# ADC.net
KiCad netlist of a schematic drawn in Altium Designer
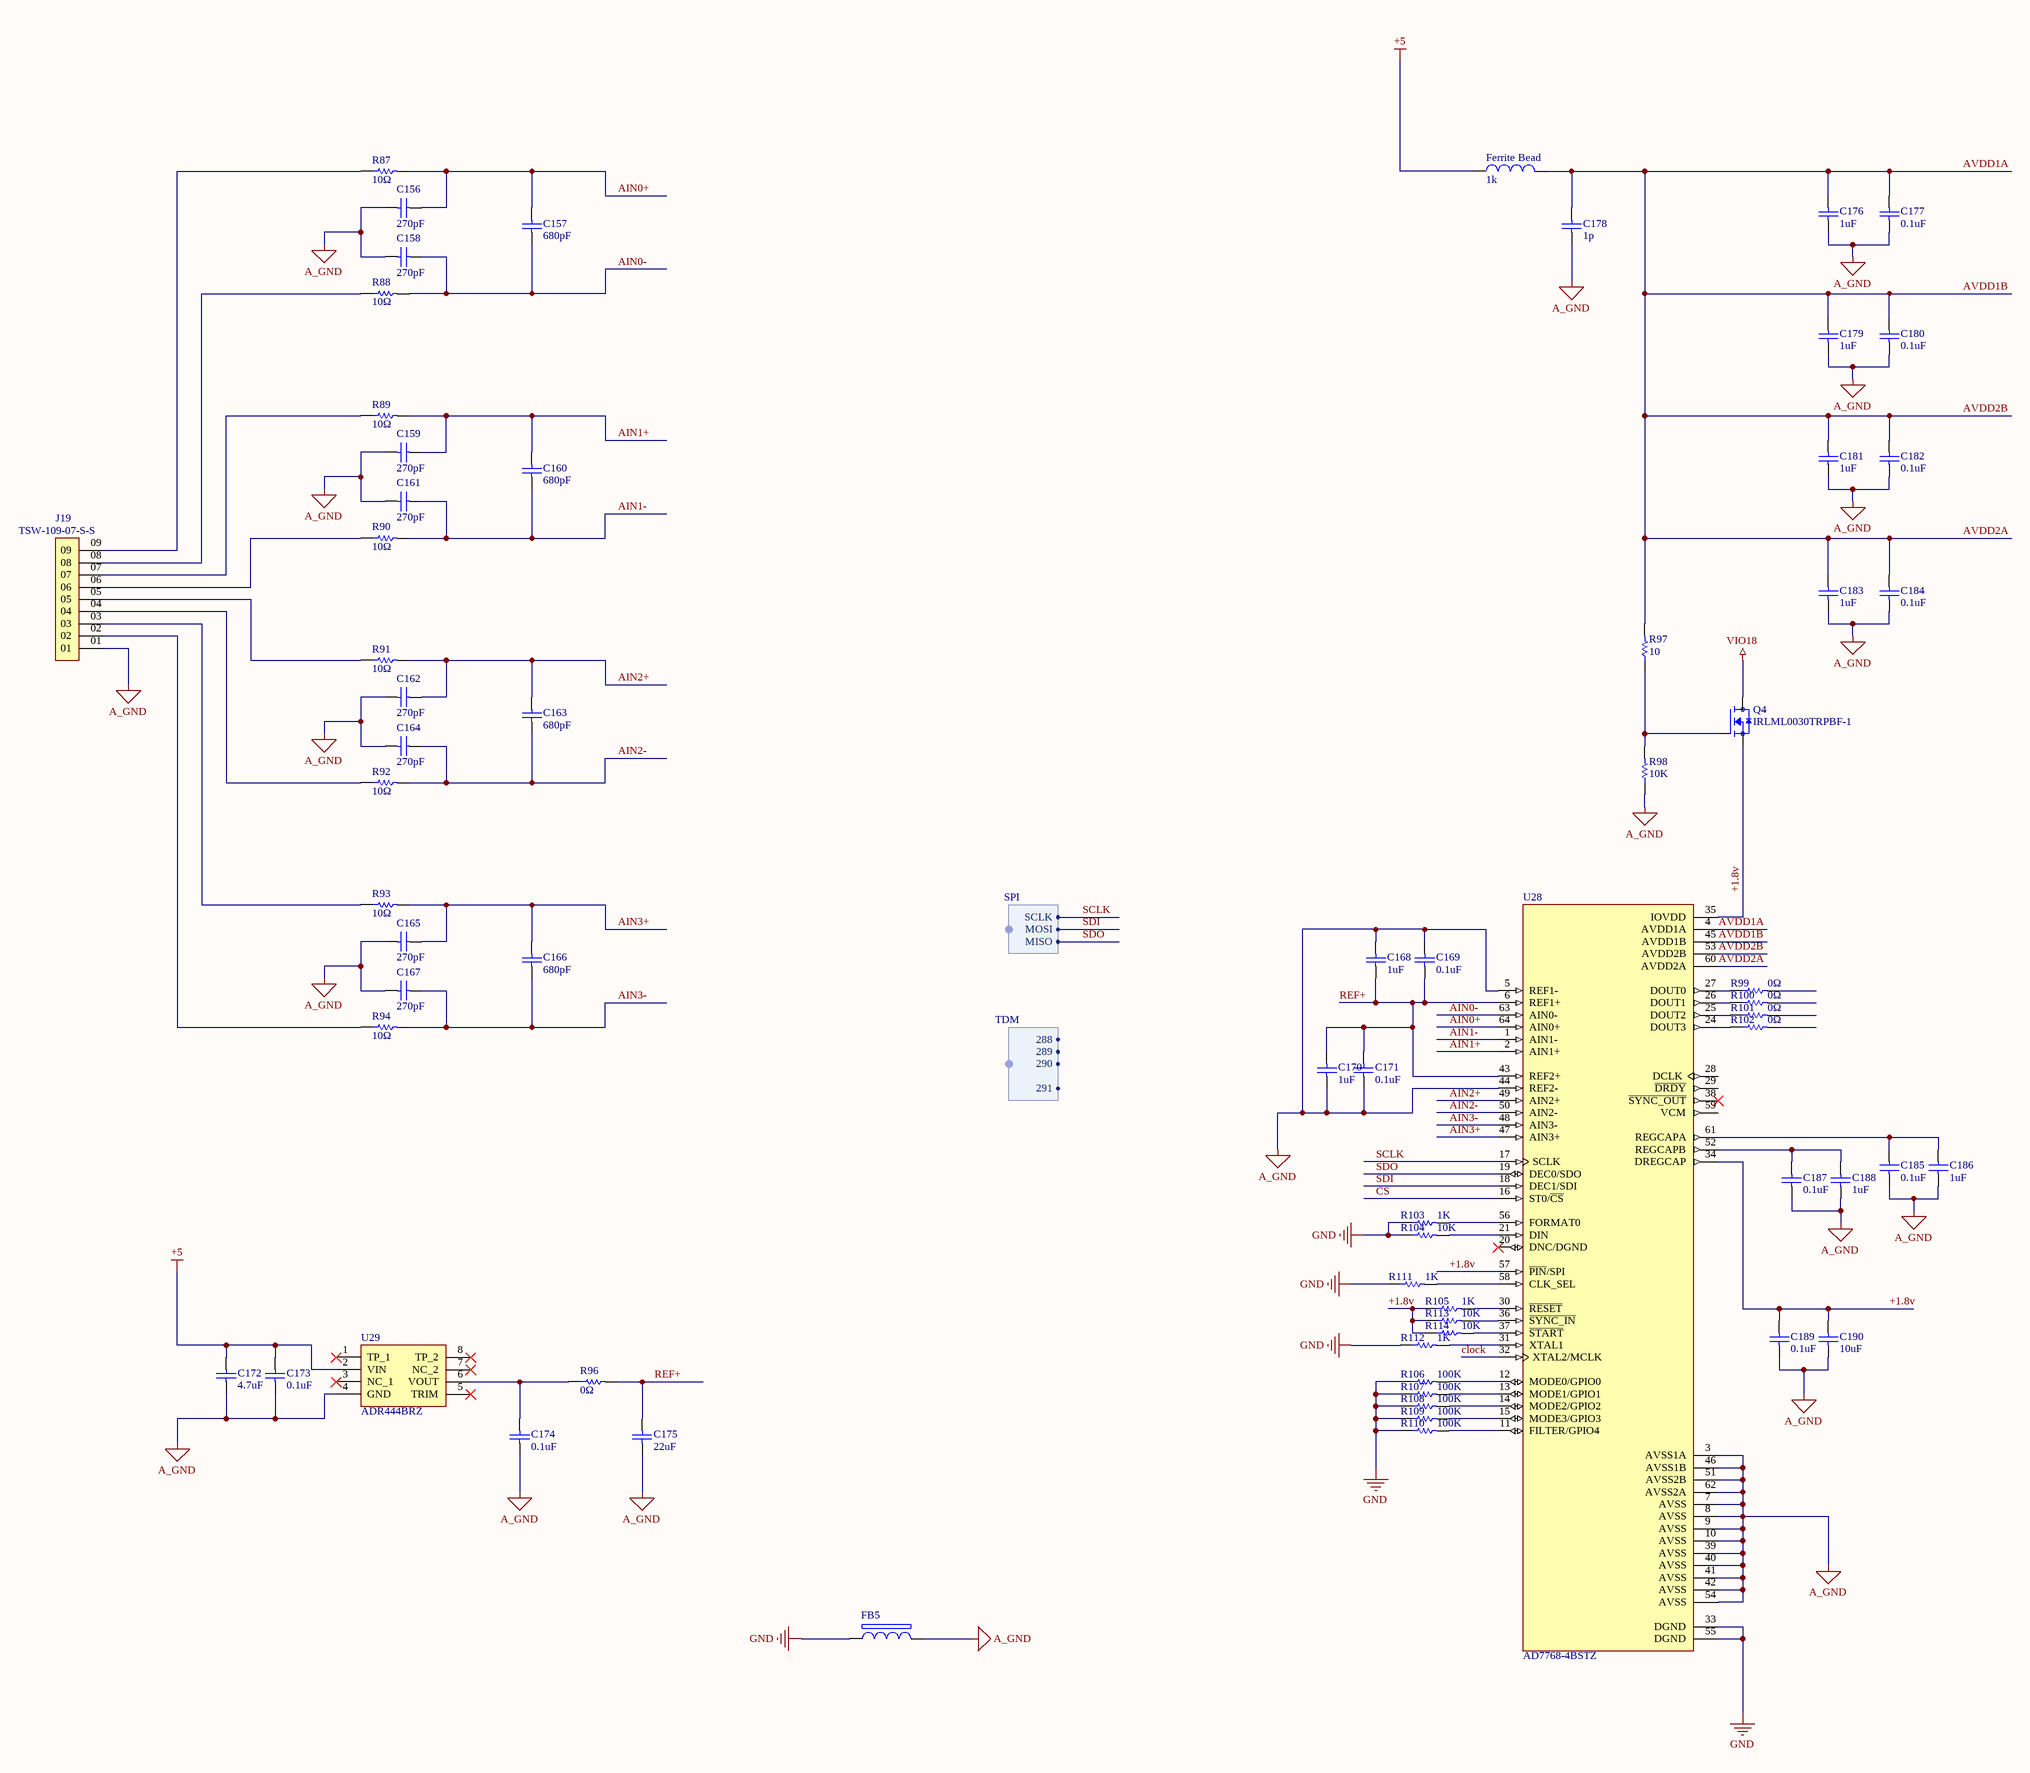
[diagram p0: ADC.SchDoc]

(export (version "E")
  (design (tool "Eeschema 10.0.6"))
  (components
    (comp (ref "C156")
      (value "270pF")
      (description "Capacitor")
      (libsource (lib "Simulation Generic Components") (part "Capacitor"))
    )
    (comp (ref "C157")
      (value "680pF")
      (description "Capacitor")
      (libsource (lib "Simulation Generic Components") (part "Capacitor"))
    )
    (comp (ref "C158")
      (value "270pF")
      (description "Capacitor")
      (libsource (lib "Simulation Generic Components") (part "Capacitor"))
    )
    (comp (ref "C159")
      (value "270pF")
      (description "Capacitor")
      (libsource (lib "Simulation Generic Components") (part "Capacitor"))
    )
    (comp (ref "C160")
      (value "680pF")
      (description "Capacitor")
      (libsource (lib "Simulation Generic Components") (part "Capacitor"))
    )
    (comp (ref "C161")
      (value "270pF")
      (description "Capacitor")
      (libsource (lib "Simulation Generic Components") (part "Capacitor"))
    )
    (comp (ref "C162")
      (value "270pF")
      (description "Capacitor")
      (libsource (lib "Simulation Generic Components") (part "Capacitor"))
    )
    (comp (ref "C163")
      (value "680pF")
      (description "Capacitor")
      (libsource (lib "Simulation Generic Components") (part "Capacitor"))
    )
    (comp (ref "C164")
      (value "270pF")
      (description "Capacitor")
      (libsource (lib "Simulation Generic Components") (part "Capacitor"))
    )
    (comp (ref "C165")
      (value "270pF")
      (description "Capacitor")
      (libsource (lib "Simulation Generic Components") (part "Capacitor"))
    )
    (comp (ref "C166")
      (value "680pF")
      (description "Capacitor")
      (libsource (lib "Simulation Generic Components") (part "Capacitor"))
    )
    (comp (ref "C167")
      (value "270pF")
      (description "Capacitor")
      (libsource (lib "Simulation Generic Components") (part "Capacitor"))
    )
    (comp (ref "C168")
      (value "1uF")
      (description "Capacitor")
      (libsource (lib "Simulation Generic Components") (part "Capacitor"))
    )
    (comp (ref "C169")
      (value "0.1uF")
      (description "Capacitor")
      (libsource (lib "Simulation Generic Components") (part "Capacitor"))
    )
    (comp (ref "C170")
      (value "1uF")
      (description "Capacitor")
      (libsource (lib "Simulation Generic Components") (part "Capacitor"))
    )
    (comp (ref "C171")
      (value "0.1uF")
      (description "Capacitor")
      (libsource (lib "Simulation Generic Components") (part "Capacitor"))
    )
    (comp (ref "C172")
      (value "4.7uF")
      (description "Capacitor")
      (libsource (lib "Simulation Generic Components") (part "Capacitor"))
    )
    (comp (ref "C173")
      (value "0.1uF")
      (description "Capacitor")
      (libsource (lib "Simulation Generic Components") (part "Capacitor"))
    )
    (comp (ref "C174")
      (value "0.1uF")
      (description "Capacitor")
      (libsource (lib "Simulation Generic Components") (part "Capacitor"))
    )
    (comp (ref "C175")
      (value "22uF")
      (description "Capacitor")
      (libsource (lib "Simulation Generic Components") (part "Capacitor"))
    )
    (comp (ref "C176")
      (value "1uF")
      (description "Capacitor")
      (libsource (lib "Simulation Generic Components") (part "Capacitor"))
    )
    (comp (ref "C177")
      (value "0.1uF")
      (description "Capacitor")
      (libsource (lib "Simulation Generic Components") (part "Capacitor"))
    )
    (comp (ref "C178")
      (value "1p")
      (description "Capacitor")
      (libsource (lib "Simulation Generic Components") (part "Capacitor"))
    )
    (comp (ref "C179")
      (value "1uF")
      (description "Capacitor")
      (libsource (lib "Simulation Generic Components") (part "Capacitor"))
    )
    (comp (ref "C180")
      (value "0.1uF")
      (description "Capacitor")
      (libsource (lib "Simulation Generic Components") (part "Capacitor"))
    )
    (comp (ref "C181")
      (value "1uF")
      (description "Capacitor")
      (libsource (lib "Simulation Generic Components") (part "Capacitor"))
    )
    (comp (ref "C182")
      (value "0.1uF")
      (description "Capacitor")
      (libsource (lib "Simulation Generic Components") (part "Capacitor"))
    )
    (comp (ref "C183")
      (value "1uF")
      (description "Capacitor")
      (libsource (lib "Simulation Generic Components") (part "Capacitor"))
    )
    (comp (ref "C184")
      (value "0.1uF")
      (description "Capacitor")
      (libsource (lib "Simulation Generic Components") (part "Capacitor"))
    )
    (comp (ref "C185")
      (value "0.1uF")
      (description "Capacitor")
      (libsource (lib "Simulation Generic Components") (part "Capacitor"))
    )
    (comp (ref "C186")
      (value "1uF")
      (description "Capacitor")
      (libsource (lib "Simulation Generic Components") (part "Capacitor"))
    )
    (comp (ref "C187")
      (value "0.1uF")
      (description "Capacitor")
      (libsource (lib "Simulation Generic Components") (part "Capacitor"))
    )
    (comp (ref "C188")
      (value "1uF")
      (description "Capacitor")
      (libsource (lib "Simulation Generic Components") (part "Capacitor"))
    )
    (comp (ref "C189")
      (value "0.1uF")
      (description "Capacitor")
      (libsource (lib "Simulation Generic Components") (part "Capacitor"))
    )
    (comp (ref "C190")
      (value "10uF")
      (description "Capacitor")
      (libsource (lib "Simulation Generic Components") (part "Capacitor"))
    )
    (comp (ref "FB5")
      (value "BLM18KG121TN1D")
      (footprint "BLM18EG101TH1D")
      (description "Ferrite Bead. 0603. 3A.  DC Resistance(DCR) 30mΩ. 120Ω@100MHz")
      (fields (field (name "MOUSER PART NUMBER") "81-BLM18KG121TN1D"))
      (libsource (lib "kit") (part "BLM18KG121TN1D"))
    )
    (comp (ref "Ferrite Bead")
      (value "1k")
      (description "Inductor")
      (libsource (lib "Simulation Generic Components") (part "Inductor"))
    )
    (comp (ref "J19")
      (value "TSW-109-07-S-S")
      (footprint "SAMTEC_TSW-109-07-S-S")
      (description "Connector Header Through Hole 9 position 0.100 (2.54mm)")
      (libsource (lib "kit") (part "TSW-109-07-S-S"))
    )
    (comp (ref "Q4")
      (value "IRLML0030TRPBF-1")
      (footprint "SOT95P237X112-3N")
      (description "Mosfet, 30v, 5.2a, 28 Mohm, 3.6 Nc Qg, Sot-23")
      (libsource (lib "kit") (part "IRLML0030TRPBF-1"))
    )
    (comp (ref "R87")
      (value "10Ω")
      (description "Resistor")
      (libsource (lib "Simulation Generic Components") (part "Resistor"))
    )
    (comp (ref "R88")
      (value "10Ω")
      (description "Resistor")
      (libsource (lib "Simulation Generic Components") (part "Resistor"))
    )
    (comp (ref "R89")
      (value "10Ω")
      (description "Resistor")
      (libsource (lib "Simulation Generic Components") (part "Resistor"))
    )
    (comp (ref "R90")
      (value "10Ω")
      (description "Resistor")
      (libsource (lib "Simulation Generic Components") (part "Resistor"))
    )
    (comp (ref "R91")
      (value "10Ω")
      (description "Resistor")
      (libsource (lib "Simulation Generic Components") (part "Resistor"))
    )
    (comp (ref "R92")
      (value "10Ω")
      (description "Resistor")
      (libsource (lib "Simulation Generic Components") (part "Resistor"))
    )
    (comp (ref "R93")
      (value "10Ω")
      (description "Resistor")
      (libsource (lib "Simulation Generic Components") (part "Resistor"))
    )
    (comp (ref "R94")
      (value "10Ω")
      (description "Resistor")
      (libsource (lib "Simulation Generic Components") (part "Resistor"))
    )
    (comp (ref "R96")
      (value "0Ω")
      (description "Resistor")
      (libsource (lib "Simulation Generic Components") (part "Resistor"))
    )
    (comp (ref "R97")
      (value "10")
      (description "Resistor")
      (libsource (lib "Simulation Generic Components") (part "Resistor"))
    )
    (comp (ref "R98")
      (value "10K")
      (description "Resistor")
      (libsource (lib "Simulation Generic Components") (part "Resistor"))
    )
    (comp (ref "R99")
      (value "0Ω")
      (description "Resistor")
      (libsource (lib "Simulation Generic Components") (part "Resistor"))
    )
    (comp (ref "R100")
      (value "0Ω")
      (description "Resistor")
      (libsource (lib "Simulation Generic Components") (part "Resistor"))
    )
    (comp (ref "R101")
      (value "0Ω")
      (description "Resistor")
      (libsource (lib "Simulation Generic Components") (part "Resistor"))
    )
    (comp (ref "R102")
      (value "0Ω")
      (description "Resistor")
      (libsource (lib "Simulation Generic Components") (part "Resistor"))
    )
    (comp (ref "R103")
      (value "1K")
      (description "Resistor")
      (libsource (lib "Simulation Generic Components") (part "Resistor"))
    )
    (comp (ref "R104")
      (value "10K")
      (description "Resistor")
      (libsource (lib "Simulation Generic Components") (part "Resistor"))
    )
    (comp (ref "R105")
      (value "1K")
      (description "Resistor")
      (libsource (lib "Simulation Generic Components") (part "Resistor"))
    )
    (comp (ref "R106")
      (value "100K")
      (description "Resistor")
      (libsource (lib "Simulation Generic Components") (part "Resistor"))
    )
    (comp (ref "R107")
      (value "100K")
      (description "Resistor")
      (libsource (lib "Simulation Generic Components") (part "Resistor"))
    )
    (comp (ref "R108")
      (value "100K")
      (description "Resistor")
      (libsource (lib "Simulation Generic Components") (part "Resistor"))
    )
    (comp (ref "R109")
      (value "100K")
      (description "Resistor")
      (libsource (lib "Simulation Generic Components") (part "Resistor"))
    )
    (comp (ref "R110")
      (value "100K")
      (description "Resistor")
      (libsource (lib "Simulation Generic Components") (part "Resistor"))
    )
    (comp (ref "R111")
      (value "1K")
      (description "Resistor")
      (libsource (lib "Simulation Generic Components") (part "Resistor"))
    )
    (comp (ref "R112")
      (value "1K")
      (description "Resistor")
      (libsource (lib "Simulation Generic Components") (part "Resistor"))
    )
    (comp (ref "R113")
      (value "10K")
      (description "Resistor")
      (libsource (lib "Simulation Generic Components") (part "Resistor"))
    )
    (comp (ref "R114")
      (value "10K")
      (description "Resistor")
      (libsource (lib "Simulation Generic Components") (part "Resistor"))
    )
    (comp (ref "U28")
      (value "AD7768-4BSTZ")
      (footprint "QFP50P1200X1200X160-64N")
      (description "4-Channel, 24-Bit, Simultaneous Sampling ADC, Power Scaling, 110.8 kHz BW")
      (libsource (lib "kit") (part "AD7768-4BSTZ"))
    )
    (comp (ref "U29")
      (value "ADR444BRZ")
      (footprint "SOIC127P600X175-8N")
      (description "Integrated Circuit")
      (fields (field (name "MOUSER PART NUMBER") "584-ADR444BRZ"))
      (libsource (lib "kit") (part "ADR444BRZ"))
    )
  )
  (nets
    (net (code "1") (name "+5") (class "Default")
      (node (ref "C172") (pin "2") (pinfunction "2_2") (pintype "passive"))
      (node (ref "C173") (pin "2") (pinfunction "2_2") (pintype "passive"))
      (node (ref "Ferrite Bead") (pin "1") (pinfunction "1_1") (pintype "passive"))
      (node (ref "U29") (pin "2") (pinfunction "VIN_2") (pintype "passive"))
    )
    (net (code "2") (name "/+1.8v") (class "Default")
      (node (ref "C189") (pin "2") (pinfunction "2_2") (pintype "passive"))
      (node (ref "C190") (pin "2") (pinfunction "2_2") (pintype "passive"))
      (node (ref "Q4") (pin "2") (pinfunction "S_2") (pintype "passive"))
      (node (ref "R105") (pin "1") (pinfunction "1_1") (pintype "passive"))
      (node (ref "R113") (pin "1") (pinfunction "1_1") (pintype "passive"))
      (node (ref "R114") (pin "1") (pinfunction "1_1") (pintype "passive"))
      (node (ref "U28") (pin "34") (pinfunction "DREGCAP_34") (pintype "output"))
      (node (ref "U28") (pin "35") (pinfunction "IOVDD_35") (pintype "power_in"))
      (node (ref "U28") (pin "57") (pinfunction "~{PIN}/SPI_57") (pintype "input"))
    )
    (net (code "3") (name "/AIN0+") (class "Default")
      (node (ref "C156") (pin "2") (pinfunction "2_2") (pintype "passive"))
      (node (ref "C157") (pin "2") (pinfunction "2_2") (pintype "passive"))
      (node (ref "R87") (pin "2") (pinfunction "2_2") (pintype "passive"))
      (node (ref "U28") (pin "64") (pinfunction "AIN0+_64") (pintype "input"))
    )
    (net (code "4") (name "/AIN0-") (class "Default")
      (node (ref "C157") (pin "1") (pinfunction "1_1") (pintype "passive"))
      (node (ref "C158") (pin "2") (pinfunction "2_2") (pintype "passive"))
      (node (ref "R88") (pin "2") (pinfunction "2_2") (pintype "passive"))
      (node (ref "U28") (pin "63") (pinfunction "AIN0-_63") (pintype "input"))
    )
    (net (code "5") (name "/AIN1+") (class "Default")
      (node (ref "C159") (pin "2") (pinfunction "2_2") (pintype "passive"))
      (node (ref "C160") (pin "2") (pinfunction "2_2") (pintype "passive"))
      (node (ref "R89") (pin "2") (pinfunction "2_2") (pintype "passive"))
      (node (ref "U28") (pin "2") (pinfunction "AIN1+_2") (pintype "input"))
    )
    (net (code "6") (name "/AIN1-") (class "Default")
      (node (ref "C160") (pin "1") (pinfunction "1_1") (pintype "passive"))
      (node (ref "C161") (pin "2") (pinfunction "2_2") (pintype "passive"))
      (node (ref "R90") (pin "2") (pinfunction "2_2") (pintype "passive"))
      (node (ref "U28") (pin "1") (pinfunction "AIN1-_1") (pintype "input"))
    )
    (net (code "7") (name "/AIN2+") (class "Default")
      (node (ref "C162") (pin "2") (pinfunction "2_2") (pintype "passive"))
      (node (ref "C163") (pin "2") (pinfunction "2_2") (pintype "passive"))
      (node (ref "R91") (pin "2") (pinfunction "2_2") (pintype "passive"))
      (node (ref "U28") (pin "49") (pinfunction "AIN2+_49") (pintype "input"))
    )
    (net (code "8") (name "/AIN2-") (class "Default")
      (node (ref "C163") (pin "1") (pinfunction "1_1") (pintype "passive"))
      (node (ref "C164") (pin "2") (pinfunction "2_2") (pintype "passive"))
      (node (ref "R92") (pin "2") (pinfunction "2_2") (pintype "passive"))
      (node (ref "U28") (pin "50") (pinfunction "AIN2-_50") (pintype "input"))
    )
    (net (code "9") (name "/AIN3+") (class "Default")
      (node (ref "C165") (pin "2") (pinfunction "2_2") (pintype "passive"))
      (node (ref "C166") (pin "2") (pinfunction "2_2") (pintype "passive"))
      (node (ref "R93") (pin "2") (pinfunction "2_2") (pintype "passive"))
      (node (ref "U28") (pin "47") (pinfunction "AIN3+_47") (pintype "input"))
    )
    (net (code "10") (name "/AIN3-") (class "Default")
      (node (ref "C166") (pin "1") (pinfunction "1_1") (pintype "passive"))
      (node (ref "C167") (pin "2") (pinfunction "2_2") (pintype "passive"))
      (node (ref "R94") (pin "2") (pinfunction "2_2") (pintype "passive"))
      (node (ref "U28") (pin "48") (pinfunction "AIN3-_48") (pintype "input"))
    )
    (net (code "11") (name "/AVDD1A") (class "Default")
      (node (ref "C176") (pin "2") (pinfunction "2_2") (pintype "passive"))
      (node (ref "C177") (pin "2") (pinfunction "2_2") (pintype "passive"))
      (node (ref "C178") (pin "1") (pinfunction "1_1") (pintype "passive"))
      (node (ref "C179") (pin "2") (pinfunction "2_2") (pintype "passive"))
      (node (ref "C180") (pin "2") (pinfunction "2_2") (pintype "passive"))
      (node (ref "C181") (pin "2") (pinfunction "2_2") (pintype "passive"))
      (node (ref "C182") (pin "2") (pinfunction "2_2") (pintype "passive"))
      (node (ref "C183") (pin "2") (pinfunction "2_2") (pintype "passive"))
      (node (ref "C184") (pin "2") (pinfunction "2_2") (pintype "passive"))
      (node (ref "Ferrite Bead") (pin "2") (pinfunction "2_2") (pintype "passive"))
      (node (ref "R97") (pin "2") (pinfunction "2_2") (pintype "passive"))
      (node (ref "U28") (pin "4") (pinfunction "AVDD1A_4") (pintype "power_in"))
      (node (ref "U28") (pin "45") (pinfunction "AVDD1B_45") (pintype "power_in"))
      (node (ref "U28") (pin "53") (pinfunction "AVDD2B_53") (pintype "power_in"))
      (node (ref "U28") (pin "60") (pinfunction "AVDD2A_60") (pintype "power_in"))
    )
    (net (code "12") (name "/CS") (class "Default")
      (node (ref "U28") (pin "16") (pinfunction "ST0/~{CS}_16") (pintype "input"))
    )
    (net (code "13") (name "/REF+") (class "Default")
      (node (ref "C168") (pin "1") (pinfunction "1_1") (pintype "passive"))
      (node (ref "C169") (pin "1") (pinfunction "1_1") (pintype "passive"))
      (node (ref "C170") (pin "2") (pinfunction "2_2") (pintype "passive"))
      (node (ref "C171") (pin "2") (pinfunction "2_2") (pintype "passive"))
      (node (ref "C175") (pin "2") (pinfunction "2_2") (pintype "passive"))
      (node (ref "R96") (pin "2") (pinfunction "2_2") (pintype "passive"))
      (node (ref "U28") (pin "43") (pinfunction "REF2+_43") (pintype "input"))
      (node (ref "U28") (pin "6") (pinfunction "REF1+_6") (pintype "input"))
    )
    (net (code "14") (name "/SCLK") (class "Default")
      (node (ref "U28") (pin "17") (pinfunction "SCLK_17") (pintype "input"))
    )
    (net (code "15") (name "/SDI") (class "Default")
      (node (ref "U28") (pin "18") (pinfunction "DEC1/SDI_18") (pintype "input"))
    )
    (net (code "16") (name "/SDO") (class "Default")
      (node (ref "U28") (pin "19") (pinfunction "DEC0/SDO_19") (pintype "bidirectional"))
    )
    (net (code "17") (name "/clock") (class "Default")
      (node (ref "U28") (pin "32") (pinfunction "XTAL2/MCLK_32") (pintype "input"))
    )
    (net (code "18") (name "A_GND") (class "Default")
      (node (ref "C156") (pin "1") (pinfunction "1_1") (pintype "passive"))
      (node (ref "C158") (pin "1") (pinfunction "1_1") (pintype "passive"))
      (node (ref "C159") (pin "1") (pinfunction "1_1") (pintype "passive"))
      (node (ref "C161") (pin "1") (pinfunction "1_1") (pintype "passive"))
      (node (ref "C162") (pin "1") (pinfunction "1_1") (pintype "passive"))
      (node (ref "C164") (pin "1") (pinfunction "1_1") (pintype "passive"))
      (node (ref "C165") (pin "1") (pinfunction "1_1") (pintype "passive"))
      (node (ref "C167") (pin "1") (pinfunction "1_1") (pintype "passive"))
      (node (ref "C168") (pin "2") (pinfunction "2_2") (pintype "passive"))
      (node (ref "C169") (pin "2") (pinfunction "2_2") (pintype "passive"))
      (node (ref "C170") (pin "1") (pinfunction "1_1") (pintype "passive"))
      (node (ref "C171") (pin "1") (pinfunction "1_1") (pintype "passive"))
      (node (ref "C172") (pin "1") (pinfunction "1_1") (pintype "passive"))
      (node (ref "C173") (pin "1") (pinfunction "1_1") (pintype "passive"))
      (node (ref "C174") (pin "1") (pinfunction "1_1") (pintype "passive"))
      (node (ref "C175") (pin "1") (pinfunction "1_1") (pintype "passive"))
      (node (ref "C176") (pin "1") (pinfunction "1_1") (pintype "passive"))
      (node (ref "C177") (pin "1") (pinfunction "1_1") (pintype "passive"))
      (node (ref "C178") (pin "2") (pinfunction "2_2") (pintype "passive"))
      (node (ref "C179") (pin "1") (pinfunction "1_1") (pintype "passive"))
      (node (ref "C180") (pin "1") (pinfunction "1_1") (pintype "passive"))
      (node (ref "C181") (pin "1") (pinfunction "1_1") (pintype "passive"))
      (node (ref "C182") (pin "1") (pinfunction "1_1") (pintype "passive"))
      (node (ref "C183") (pin "1") (pinfunction "1_1") (pintype "passive"))
      (node (ref "C184") (pin "1") (pinfunction "1_1") (pintype "passive"))
      (node (ref "C185") (pin "1") (pinfunction "1_1") (pintype "passive"))
      (node (ref "C186") (pin "1") (pinfunction "1_1") (pintype "passive"))
      (node (ref "C187") (pin "1") (pinfunction "1_1") (pintype "passive"))
      (node (ref "C188") (pin "1") (pinfunction "1_1") (pintype "passive"))
      (node (ref "C189") (pin "1") (pinfunction "1_1") (pintype "passive"))
      (node (ref "C190") (pin "1") (pinfunction "1_1") (pintype "passive"))
      (node (ref "FB5") (pin "2") (pinfunction "2_2") (pintype "passive"))
      (node (ref "J19") (pin "01") (pinfunction "01_01") (pintype "passive"))
      (node (ref "R98") (pin "1") (pinfunction "1_1") (pintype "passive"))
      (node (ref "U28") (pin "10") (pinfunction "AVSS_10") (pintype "power_in"))
      (node (ref "U28") (pin "3") (pinfunction "AVSS1A_3") (pintype "power_in"))
      (node (ref "U28") (pin "39") (pinfunction "AVSS_39") (pintype "power_in"))
      (node (ref "U28") (pin "40") (pinfunction "AVSS_40") (pintype "power_in"))
      (node (ref "U28") (pin "41") (pinfunction "AVSS_41") (pintype "power_in"))
      (node (ref "U28") (pin "42") (pinfunction "AVSS_42") (pintype "power_in"))
      (node (ref "U28") (pin "44") (pinfunction "REF2-_44") (pintype "input"))
      (node (ref "U28") (pin "46") (pinfunction "AVSS1B_46") (pintype "power_in"))
      (node (ref "U28") (pin "5") (pinfunction "REF1-_5") (pintype "input"))
      (node (ref "U28") (pin "51") (pinfunction "AVSS2B_51") (pintype "power_in"))
      (node (ref "U28") (pin "54") (pinfunction "AVSS_54") (pintype "power_in"))
      (node (ref "U28") (pin "62") (pinfunction "AVSS2A_62") (pintype "power_in"))
      (node (ref "U28") (pin "7") (pinfunction "AVSS_7") (pintype "power_in"))
      (node (ref "U28") (pin "8") (pinfunction "AVSS_8") (pintype "power_in"))
      (node (ref "U28") (pin "9") (pinfunction "AVSS_9") (pintype "power_in"))
      (node (ref "U29") (pin "4") (pinfunction "GND_4") (pintype "passive"))
    )
    (net (code "19") (name "GND") (class "Default")
      (node (ref "FB5") (pin "1") (pinfunction "1_1") (pintype "passive"))
      (node (ref "R103") (pin "1") (pinfunction "1_1") (pintype "passive"))
      (node (ref "R104") (pin "1") (pinfunction "1_1") (pintype "passive"))
      (node (ref "R106") (pin "1") (pinfunction "1_1") (pintype "passive"))
      (node (ref "R107") (pin "1") (pinfunction "1_1") (pintype "passive"))
      (node (ref "R108") (pin "1") (pinfunction "1_1") (pintype "passive"))
      (node (ref "R109") (pin "1") (pinfunction "1_1") (pintype "passive"))
      (node (ref "R110") (pin "1") (pinfunction "1_1") (pintype "passive"))
      (node (ref "R111") (pin "1") (pinfunction "1_1") (pintype "passive"))
      (node (ref "R112") (pin "1") (pinfunction "1_1") (pintype "passive"))
      (node (ref "U28") (pin "33") (pinfunction "DGND_33") (pintype "power_in"))
      (node (ref "U28") (pin "55") (pinfunction "DGND_55") (pintype "power_in"))
    )
    (net (code "20") (name "Net-(J19-Pad02)") (class "Default")
      (node (ref "J19") (pin "02") (pinfunction "02_02") (pintype "passive"))
      (node (ref "R94") (pin "1") (pinfunction "1_1") (pintype "passive"))
    )
    (net (code "21") (name "Net-(J19-Pad03)") (class "Default")
      (node (ref "J19") (pin "03") (pinfunction "03_03") (pintype "passive"))
      (node (ref "R93") (pin "1") (pinfunction "1_1") (pintype "passive"))
    )
    (net (code "22") (name "Net-(J19-Pad04)") (class "Default")
      (node (ref "J19") (pin "04") (pinfunction "04_04") (pintype "passive"))
      (node (ref "R92") (pin "1") (pinfunction "1_1") (pintype "passive"))
    )
    (net (code "23") (name "Net-(J19-Pad05)") (class "Default")
      (node (ref "J19") (pin "05") (pinfunction "05_05") (pintype "passive"))
      (node (ref "R91") (pin "1") (pinfunction "1_1") (pintype "passive"))
    )
    (net (code "24") (name "Net-(J19-Pad06)") (class "Default")
      (node (ref "J19") (pin "06") (pinfunction "06_06") (pintype "passive"))
      (node (ref "R90") (pin "1") (pinfunction "1_1") (pintype "passive"))
    )
    (net (code "25") (name "Net-(J19-Pad07)") (class "Default")
      (node (ref "J19") (pin "07") (pinfunction "07_07") (pintype "passive"))
      (node (ref "R89") (pin "1") (pinfunction "1_1") (pintype "passive"))
    )
    (net (code "26") (name "Net-(J19-Pad08)") (class "Default")
      (node (ref "J19") (pin "08") (pinfunction "08_08") (pintype "passive"))
      (node (ref "R88") (pin "1") (pinfunction "1_1") (pintype "passive"))
    )
    (net (code "27") (name "Net-(J19-Pad09)") (class "Default")
      (node (ref "J19") (pin "09") (pinfunction "09_09") (pintype "passive"))
      (node (ref "R87") (pin "1") (pinfunction "1_1") (pintype "passive"))
    )
    (net (code "28") (name "Net-(Q4-G)") (class "Default")
      (node (ref "Q4") (pin "1") (pinfunction "G_1") (pintype "passive"))
      (node (ref "R97") (pin "1") (pinfunction "1_1") (pintype "passive"))
      (node (ref "R98") (pin "2") (pinfunction "2_2") (pintype "passive"))
    )
    (net (code "29") (name "Net-(U28-CLK_SEL)") (class "Default")
      (node (ref "R111") (pin "2") (pinfunction "2_2") (pintype "passive"))
      (node (ref "U28") (pin "58") (pinfunction "CLK_SEL_58") (pintype "input"))
    )
    (net (code "30") (name "Net-(U28-DIN)") (class "Default")
      (node (ref "R104") (pin "2") (pinfunction "2_2") (pintype "passive"))
      (node (ref "U28") (pin "21") (pinfunction "DIN_21") (pintype "input"))
    )
    (net (code "31") (name "Net-(U28-DOUT0)") (class "Default")
      (node (ref "R99") (pin "1") (pinfunction "1_1") (pintype "passive"))
      (node (ref "U28") (pin "27") (pinfunction "DOUT0_27") (pintype "output"))
    )
    (net (code "32") (name "Net-(U28-DOUT1)") (class "Default")
      (node (ref "R100") (pin "1") (pinfunction "1_1") (pintype "passive"))
      (node (ref "U28") (pin "26") (pinfunction "DOUT1_26") (pintype "output"))
    )
    (net (code "33") (name "Net-(U28-DOUT2)") (class "Default")
      (node (ref "R101") (pin "1") (pinfunction "1_1") (pintype "passive"))
      (node (ref "U28") (pin "25") (pinfunction "DOUT2_25") (pintype "output"))
    )
    (net (code "34") (name "Net-(U28-DOUT3)") (class "Default")
      (node (ref "R102") (pin "1") (pinfunction "1_1") (pintype "passive"))
      (node (ref "U28") (pin "24") (pinfunction "DOUT3_24") (pintype "output"))
    )
    (net (code "35") (name "Net-(U28-FILTER{slash}GPIO4)") (class "Default")
      (node (ref "R110") (pin "2") (pinfunction "2_2") (pintype "passive"))
      (node (ref "U28") (pin "11") (pinfunction "FILTER/GPIO4_11") (pintype "bidirectional"))
    )
    (net (code "36") (name "Net-(U28-FORMAT0)") (class "Default")
      (node (ref "R103") (pin "2") (pinfunction "2_2") (pintype "passive"))
      (node (ref "U28") (pin "56") (pinfunction "FORMAT0_56") (pintype "input"))
    )
    (net (code "37") (name "Net-(U28-MODE0{slash}GPIO0)") (class "Default")
      (node (ref "R106") (pin "2") (pinfunction "2_2") (pintype "passive"))
      (node (ref "U28") (pin "12") (pinfunction "MODE0/GPIO0_12") (pintype "bidirectional"))
    )
    (net (code "38") (name "Net-(U28-MODE1{slash}GPIO1)") (class "Default")
      (node (ref "R107") (pin "2") (pinfunction "2_2") (pintype "passive"))
      (node (ref "U28") (pin "13") (pinfunction "MODE1/GPIO1_13") (pintype "bidirectional"))
    )
    (net (code "39") (name "Net-(U28-MODE2{slash}GPIO2)") (class "Default")
      (node (ref "R108") (pin "2") (pinfunction "2_2") (pintype "passive"))
      (node (ref "U28") (pin "14") (pinfunction "MODE2/GPIO2_14") (pintype "bidirectional"))
    )
    (net (code "40") (name "Net-(U28-MODE3{slash}GPIO3)") (class "Default")
      (node (ref "R109") (pin "2") (pinfunction "2_2") (pintype "passive"))
      (node (ref "U28") (pin "15") (pinfunction "MODE3/GPIO3_15") (pintype "bidirectional"))
    )
    (net (code "41") (name "Net-(U28-REGCAPA)") (class "Default")
      (node (ref "C185") (pin "2") (pinfunction "2_2") (pintype "passive"))
      (node (ref "C186") (pin "2") (pinfunction "2_2") (pintype "passive"))
      (node (ref "U28") (pin "61") (pinfunction "REGCAPA_61") (pintype "output"))
    )
    (net (code "42") (name "Net-(U28-REGCAPB)") (class "Default")
      (node (ref "C187") (pin "2") (pinfunction "2_2") (pintype "passive"))
      (node (ref "C188") (pin "2") (pinfunction "2_2") (pintype "passive"))
      (node (ref "U28") (pin "52") (pinfunction "REGCAPB_52") (pintype "output"))
    )
    (net (code "43") (name "Net-(U28-XTAL1)") (class "Default")
      (node (ref "R112") (pin "2") (pinfunction "2_2") (pintype "passive"))
      (node (ref "U28") (pin "31") (pinfunction "XTAL1_31") (pintype "input"))
    )
    (net (code "44") (name "Net-(U28-~{RESET})") (class "Default")
      (node (ref "R105") (pin "2") (pinfunction "2_2") (pintype "passive"))
      (node (ref "U28") (pin "30") (pinfunction "~{RESET}_30") (pintype "input"))
    )
    (net (code "45") (name "Net-(U28-~{START})") (class "Default")
      (node (ref "R114") (pin "2") (pinfunction "2_2") (pintype "passive"))
      (node (ref "U28") (pin "37") (pinfunction "~{START}_37") (pintype "input"))
    )
    (net (code "46") (name "Net-(U28-~{SYNC_IN})") (class "Default")
      (node (ref "R113") (pin "2") (pinfunction "2_2") (pintype "passive"))
      (node (ref "U28") (pin "36") (pinfunction "~{SYNC_IN}_36") (pintype "input"))
    )
    (net (code "47") (name "Net-(U29-VOUT)") (class "Default")
      (node (ref "C174") (pin "2") (pinfunction "2_2") (pintype "passive"))
      (node (ref "R96") (pin "1") (pinfunction "1_1") (pintype "passive"))
      (node (ref "U29") (pin "6") (pinfunction "VOUT_6") (pintype "passive"))
    )
    (net (code "48") (name "VIO18") (class "Default")
      (node (ref "Q4") (pin "3") (pinfunction "D_3") (pintype "passive"))
    )
    (net (code "49") (name "unconnected-(R99-Pad2)") (class "Default")
      (node (ref "R99") (pin "2") (pinfunction "2_2") (pintype "passive"))
    )
    (net (code "50") (name "unconnected-(R100-Pad2)") (class "Default")
      (node (ref "R100") (pin "2") (pinfunction "2_2") (pintype "passive"))
    )
    (net (code "51") (name "unconnected-(R101-Pad2)") (class "Default")
      (node (ref "R101") (pin "2") (pinfunction "2_2") (pintype "passive"))
    )
    (net (code "52") (name "unconnected-(R102-Pad2)") (class "Default")
      (node (ref "R102") (pin "2") (pinfunction "2_2") (pintype "passive"))
    )
    (net (code "53") (name "unconnected-(U28-DCLK-Pad28)") (class "Default")
      (node (ref "U28") (pin "28") (pinfunction "DCLK_28") (pintype "output"))
    )
    (net (code "54") (name "unconnected-(U28-DNC{slash}DGND-Pad20)") (class "Default")
      (node (ref "U28") (pin "20") (pinfunction "DNC/DGND_20") (pintype "bidirectional+no_connect"))
    )
    (net (code "55") (name "unconnected-(U28-VCM-Pad59)") (class "Default")
      (node (ref "U28") (pin "59") (pinfunction "VCM_59") (pintype "output"))
    )
    (net (code "56") (name "unconnected-(U28-~{DRDY}-Pad29)") (class "Default")
      (node (ref "U28") (pin "29") (pinfunction "~{DRDY}_29") (pintype "output"))
    )
    (net (code "57") (name "unconnected-(U28-~{SYNC_OUT}-Pad38)") (class "Default")
      (node (ref "U28") (pin "38") (pinfunction "~{SYNC_OUT}_38") (pintype "output+no_connect"))
    )
    (net (code "58") (name "unconnected-(U29-NC_1-Pad3)") (class "Default")
      (node (ref "U29") (pin "3") (pinfunction "NC_1_3") (pintype "passive+no_connect"))
    )
    (net (code "59") (name "unconnected-(U29-NC_2-Pad7)") (class "Default")
      (node (ref "U29") (pin "7") (pinfunction "NC_2_7") (pintype "passive+no_connect"))
    )
    (net (code "60") (name "unconnected-(U29-TP_1-Pad1)") (class "Default")
      (node (ref "U29") (pin "1") (pinfunction "TP_1_1") (pintype "passive+no_connect"))
    )
    (net (code "61") (name "unconnected-(U29-TP_2-Pad8)") (class "Default")
      (node (ref "U29") (pin "8") (pinfunction "TP_2_8") (pintype "passive+no_connect"))
    )
    (net (code "62") (name "unconnected-(U29-TRIM-Pad5)") (class "Default")
      (node (ref "U29") (pin "5") (pinfunction "TRIM_5") (pintype "passive+no_connect"))
    )
  )
)
